# dhtxx_heater.net
KiCad netlist of a schematic drawn in EAGLE
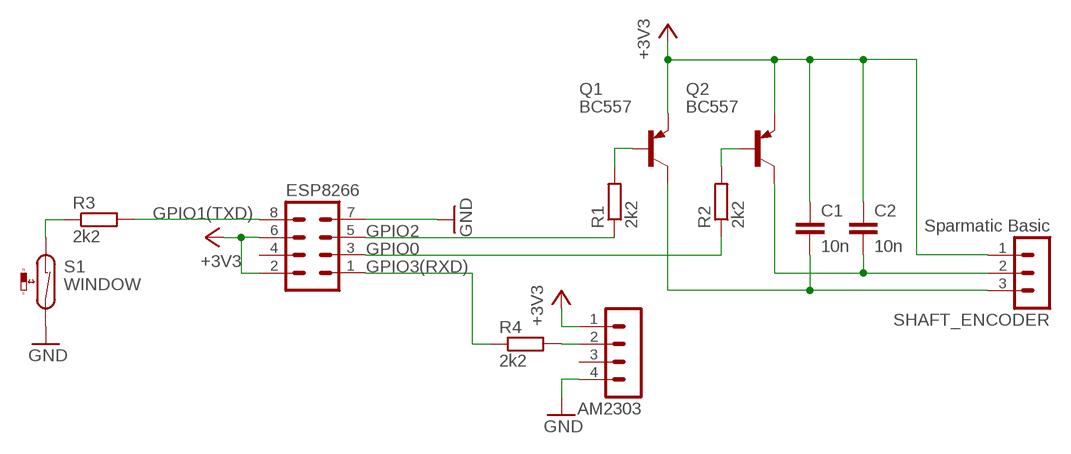
[diagram p0: schematic, sheet 1]

(export (version "E")
  (design (tool "Eeschema 10.0.6"))
  (components
    (comp (ref "AM2303")
      (value "MA04-1")
      (footprint "eagle-import:MA04-1")
      (libsource (lib "eagle-import") (part "MA04-1"))
    )
    (comp (ref "C1")
      (value "10n")
      (footprint "eagle-import:C075-032X103")
      (libsource (lib "eagle-import") (part "C-EU075-032X103"))
    )
    (comp (ref "C2")
      (value "10n")
      (footprint "eagle-import:C075-032X103")
      (libsource (lib "eagle-import") (part "C-EU075-032X103"))
    )
    (comp (ref "ESP8266")
      (value "MA04-2")
      (footprint "eagle-import:MA04-2")
      (libsource (lib "eagle-import") (part "MA04-2"))
    )
    (comp (ref "Q1")
      (value "BC557")
      (footprint "eagle-import:TO92-EBC")
      (libsource (lib "eagle-import") (part "BC557"))
    )
    (comp (ref "Q2")
      (value "BC557")
      (footprint "eagle-import:TO92-EBC")
      (libsource (lib "eagle-import") (part "BC557"))
    )
    (comp (ref "R1")
      (value "2k2")
      (footprint "eagle-import:0204_7")
      (libsource (lib "eagle-import") (part "R-EU_0204/7"))
    )
    (comp (ref "R2")
      (value "2k2")
      (footprint "eagle-import:0204_7")
      (libsource (lib "eagle-import") (part "R-EU_0204/7"))
    )
    (comp (ref "R3")
      (value "2k2")
      (footprint "eagle-import:0204_7")
      (libsource (lib "eagle-import") (part "R-EU_0204/7"))
    )
    (comp (ref "R4")
      (value "2k2")
      (footprint "eagle-import:0204_7")
      (libsource (lib "eagle-import") (part "R-EU_0204/7"))
    )
    (comp (ref "S1")
      (value "WINDOW")
      (footprint "eagle-import:MK6-8-A")
      (fields (field (name "MF") "MEDER") (field (name "MPN") "MK6-8-H"))
      (libsource (lib "eagle-import") (part "REED-SWITCH-MK6-8-H"))
    )
    (comp (ref "SHAFT_ENCODER")
      (value "Sparmatic Basic")
      (footprint "eagle-import:MA03-1")
      (libsource (lib "eagle-import") (part "MA03-1"))
    )
  )
  (nets
    (net (code "1") (name "+3V3") (class "Default")
      (node (ref "AM2303") (pin "1") (pinfunction "1_1") (pintype "passive"))
      (node (ref "C1") (pin "1") (pinfunction "1_1") (pintype "passive"))
      (node (ref "C2") (pin "1") (pinfunction "1_1") (pintype "passive"))
      (node (ref "ESP8266") (pin "2") (pinfunction "2_2") (pintype "passive"))
      (node (ref "ESP8266") (pin "6") (pinfunction "6_6") (pintype "passive"))
      (node (ref "Q1") (pin "E") (pinfunction "E_E") (pintype "passive"))
      (node (ref "Q2") (pin "E") (pinfunction "E_E") (pintype "passive"))
      (node (ref "SHAFT_ENCODER") (pin "1") (pinfunction "1_1") (pintype "passive"))
    )
    (net (code "2") (name "/GPIO0") (class "Default")
      (node (ref "ESP8266") (pin "3") (pinfunction "3_3") (pintype "passive"))
      (node (ref "R2") (pin "1") (pinfunction "1_1") (pintype "passive"))
    )
    (net (code "3") (name "/GPIO1(TXD)") (class "Default")
      (node (ref "ESP8266") (pin "8") (pinfunction "8_8") (pintype "passive"))
      (node (ref "R3") (pin "2") (pinfunction "2_2") (pintype "passive"))
    )
    (net (code "4") (name "/GPIO2") (class "Default")
      (node (ref "ESP8266") (pin "5") (pinfunction "5_5") (pintype "passive"))
      (node (ref "R1") (pin "1") (pinfunction "1_1") (pintype "passive"))
    )
    (net (code "5") (name "/GPIO3(RXD)") (class "Default")
      (node (ref "ESP8266") (pin "1") (pinfunction "1_1") (pintype "passive"))
      (node (ref "R4") (pin "1") (pinfunction "1_1") (pintype "passive"))
    )
    (net (code "6") (name "GND") (class "Default")
      (node (ref "AM2303") (pin "4") (pinfunction "4_4") (pintype "passive"))
      (node (ref "ESP8266") (pin "7") (pinfunction "7_7") (pintype "passive"))
      (node (ref "S1") (pin "2") (pinfunction "2_2") (pintype "passive"))
    )
    (net (code "7") (name "Net-(AM2303-Pad2)") (class "Default")
      (node (ref "AM2303") (pin "2") (pinfunction "2_2") (pintype "passive"))
      (node (ref "R4") (pin "2") (pinfunction "2_2") (pintype "passive"))
    )
    (net (code "8") (name "Net-(C1-Pad2)") (class "Default")
      (node (ref "C1") (pin "2") (pinfunction "2_2") (pintype "passive"))
      (node (ref "Q1") (pin "C") (pinfunction "C_C") (pintype "passive"))
      (node (ref "SHAFT_ENCODER") (pin "3") (pinfunction "3_3") (pintype "passive"))
    )
    (net (code "9") (name "Net-(C2-Pad2)") (class "Default")
      (node (ref "C2") (pin "2") (pinfunction "2_2") (pintype "passive"))
      (node (ref "Q2") (pin "C") (pinfunction "C_C") (pintype "passive"))
      (node (ref "SHAFT_ENCODER") (pin "2") (pinfunction "2_2") (pintype "passive"))
    )
    (net (code "10") (name "Net-(Q1-PadB)") (class "Default")
      (node (ref "Q1") (pin "B") (pinfunction "B_B") (pintype "passive"))
      (node (ref "R1") (pin "2") (pinfunction "2_2") (pintype "passive"))
    )
    (net (code "11") (name "Net-(Q2-PadB)") (class "Default")
      (node (ref "Q2") (pin "B") (pinfunction "B_B") (pintype "passive"))
      (node (ref "R2") (pin "2") (pinfunction "2_2") (pintype "passive"))
    )
    (net (code "12") (name "Net-(R3-Pad1)") (class "Default")
      (node (ref "R3") (pin "1") (pinfunction "1_1") (pintype "passive"))
      (node (ref "S1") (pin "1") (pinfunction "1_1") (pintype "passive"))
    )
    (net (code "13") (name "unconnected-(AM2303-Pad3)") (class "Default")
      (node (ref "AM2303") (pin "3") (pinfunction "3_3") (pintype "passive"))
    )
    (net (code "14") (name "unconnected-(ESP8266-Pad4)") (class "Default")
      (node (ref "ESP8266") (pin "4") (pinfunction "4_4") (pintype "passive"))
    )
  )
)
